# Talko_1_1.net
KiCad netlist of a schematic drawn in EAGLE
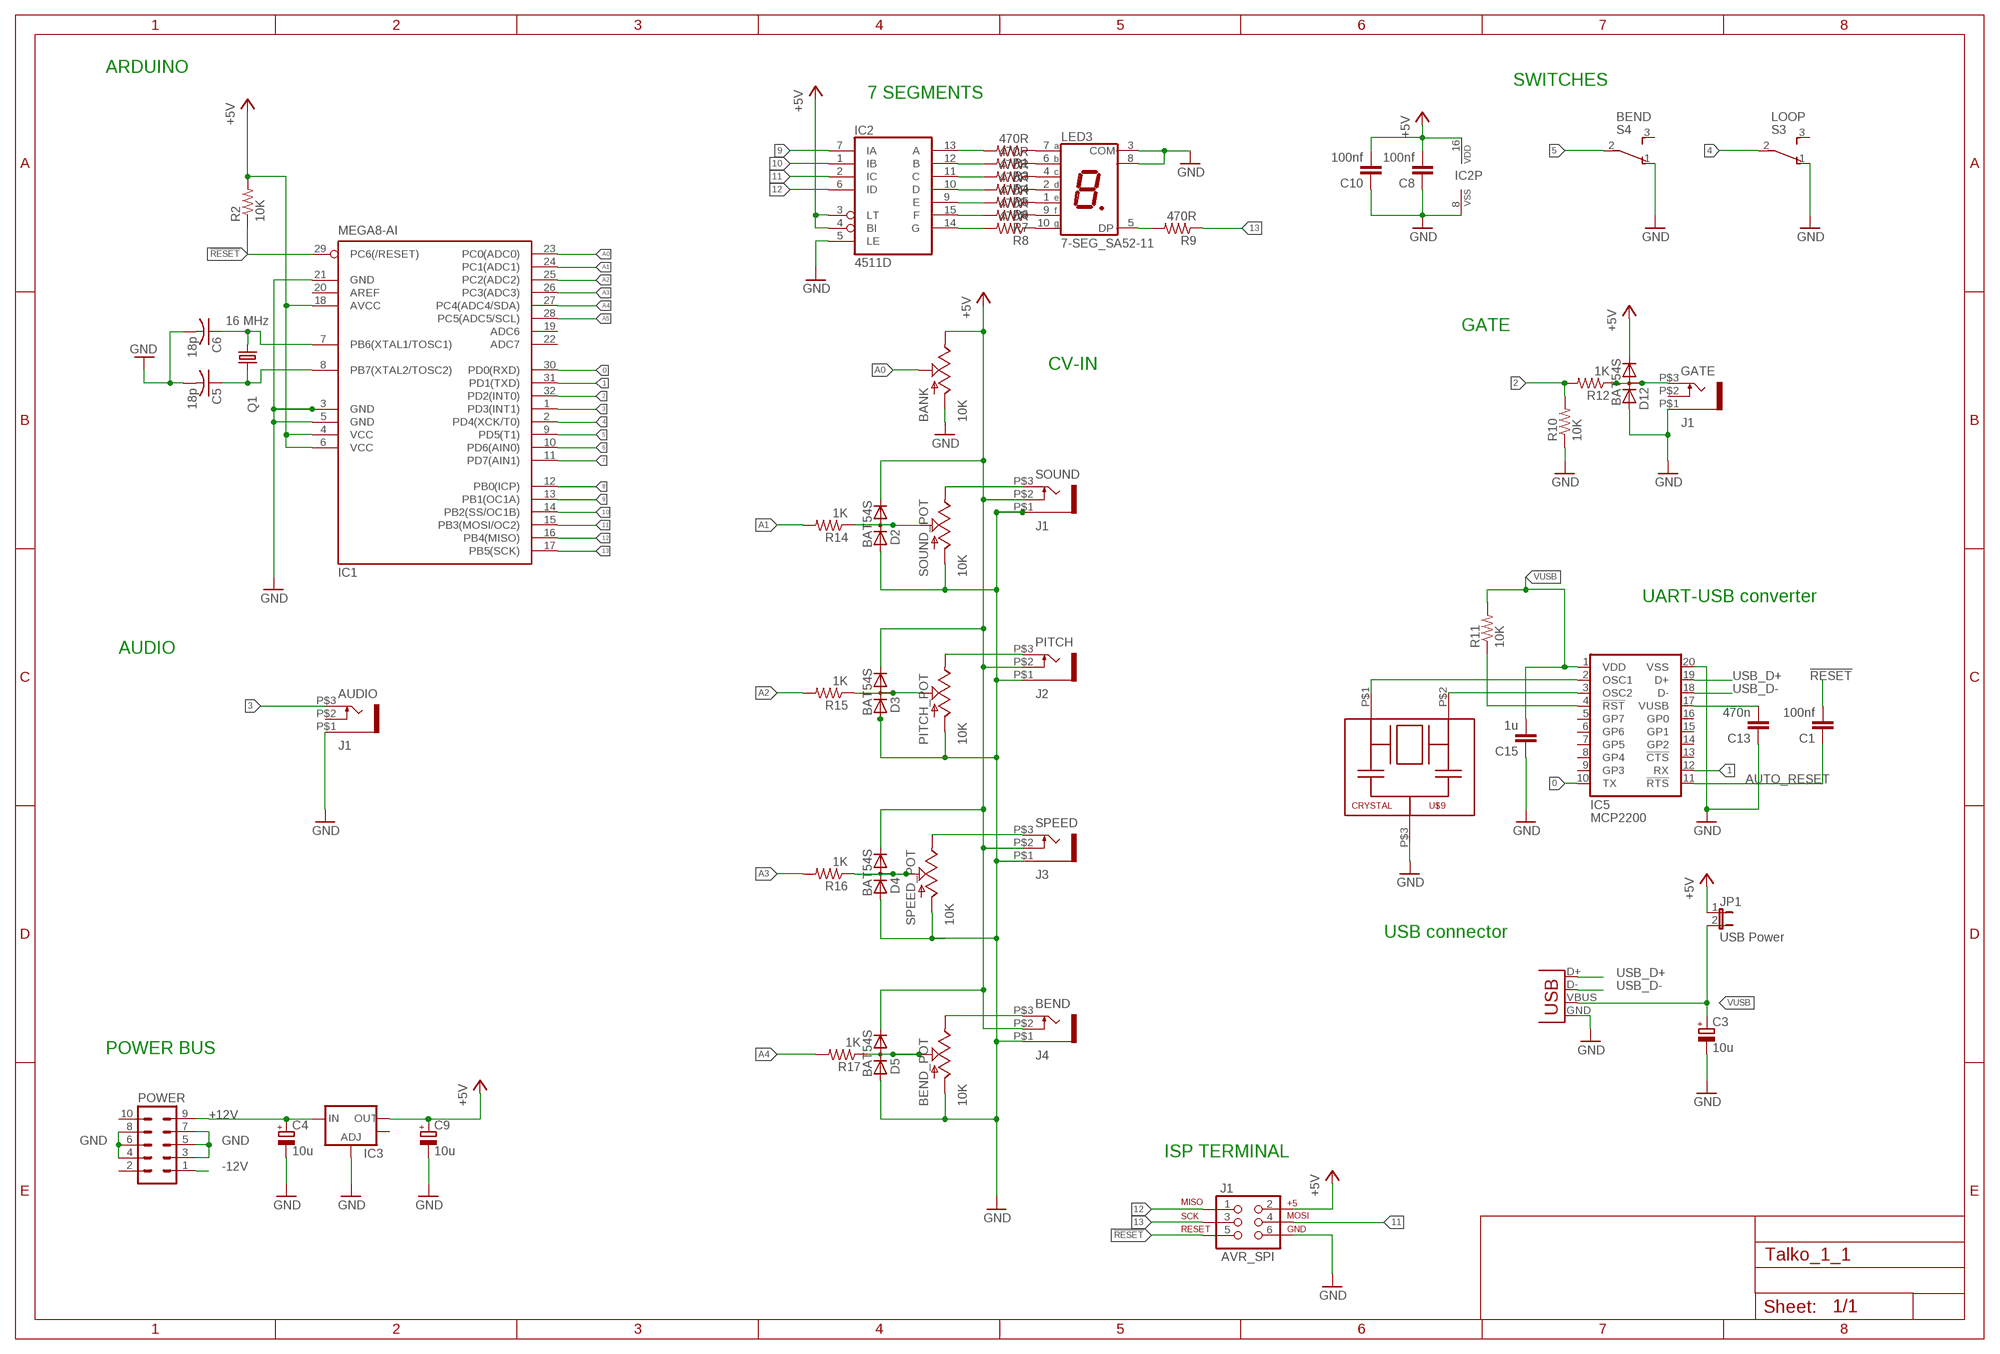
[diagram p0: schematic, sheet 1]

(export (version "E")
  (design (tool "Eeschema 10.0.6"))
  (components
    (comp (ref "AUDIO")
      (value "J1")
      (footprint "eagle-import:THONKICONN")
      (libsource (lib "eagle-import") (part "THONKICONN"))
    )
    (comp (ref "BANK")
      (value "10K")
      (footprint "eagle-import:ALPS_POT")
      (libsource (lib "eagle-import") (part "POT"))
    )
    (comp (ref "BEND")
      (value "J4")
      (footprint "eagle-import:THONKICONN")
      (libsource (lib "eagle-import") (part "THONKICONN"))
    )
    (comp (ref "BEND_POT")
      (value "10K")
      (footprint "eagle-import:ALPS_POT")
      (libsource (lib "eagle-import") (part "POT"))
    )
    (comp (ref "C1")
      (value "100nf")
      (footprint "eagle-import:C0805")
      (libsource (lib "eagle-import") (part "C-EUC0805"))
    )
    (comp (ref "C3")
      (value "10u")
      (footprint "eagle-import:R_2012-12R")
      (libsource (lib "eagle-import") (part "CPOL-EUR/2012-12R"))
    )
    (comp (ref "C4")
      (value "10u")
      (footprint "eagle-import:R_2012-12R")
      (libsource (lib "eagle-import") (part "CPOL-EUR/2012-12R"))
    )
    (comp (ref "C5")
      (value "18p")
      (footprint "eagle-import:C0805K")
      (libsource (lib "eagle-import") (part "C-USC0805K"))
    )
    (comp (ref "C6")
      (value "18p")
      (footprint "eagle-import:C0805K")
      (libsource (lib "eagle-import") (part "C-USC0805K"))
    )
    (comp (ref "C8")
      (value "100nf")
      (footprint "eagle-import:C0805")
      (libsource (lib "eagle-import") (part "C-EUC0805"))
    )
    (comp (ref "C9")
      (value "10u")
      (footprint "eagle-import:R_2012-12R")
      (libsource (lib "eagle-import") (part "CPOL-EUR/2012-12R"))
    )
    (comp (ref "C10")
      (value "100nf")
      (footprint "eagle-import:C0805")
      (libsource (lib "eagle-import") (part "C-EUC0805"))
    )
    (comp (ref "C13")
      (value "470n")
      (footprint "eagle-import:0805")
      (libsource (lib "eagle-import") (part "CAP0805"))
    )
    (comp (ref "C15")
      (value "1u")
      (footprint "eagle-import:0805")
      (libsource (lib "eagle-import") (part "CAP0805"))
    )
    (comp (ref "D2")
      (value "BAT54S")
      (footprint "eagle-import:SOT23")
      (libsource (lib "eagle-import") (part "DIODE_2CACA-SOT23"))
    )
    (comp (ref "D3")
      (value "BAT54S")
      (footprint "eagle-import:SOT23")
      (libsource (lib "eagle-import") (part "DIODE_2CACA-SOT23"))
    )
    (comp (ref "D4")
      (value "BAT54S")
      (footprint "eagle-import:SOT23")
      (libsource (lib "eagle-import") (part "DIODE_2CACA-SOT23"))
    )
    (comp (ref "D5")
      (value "BAT54S")
      (footprint "eagle-import:SOT23")
      (libsource (lib "eagle-import") (part "DIODE_2CACA-SOT23"))
    )
    (comp (ref "D12")
      (value "BAT54S")
      (footprint "eagle-import:SOT23")
      (libsource (lib "eagle-import") (part "DIODE_2CACA-SOT23"))
    )
    (comp (ref "GATE")
      (value "J1")
      (footprint "eagle-import:THONKICONN")
      (libsource (lib "eagle-import") (part "THONKICONN"))
    )
    (comp (ref "IC1")
      (value "MEGA8-AI")
      (footprint "eagle-import:TQFP32-08")
      (fields (field (name "MPN") "ATMEGA8-16AU"))
      (libsource (lib "eagle-import") (part "MEGA8-AI"))
    )
    (comp (ref "IC2")
      (value "4511D")
      (footprint "eagle-import:SO16")
      (fields (field (name "OC_MOUSER") "863-MC14511BDG"))
      (libsource (lib "eagle-import") (part "4511D"))
    )
    (comp (ref "IC3")
      (value "V_REG_LM1117SOT223")
      (footprint "eagle-import:SOT223")
      (libsource (lib "eagle-import") (part "V_REG_LM1117SOT223"))
    )
    (comp (ref "IC5")
      (value "MCP2200")
      (footprint "eagle-import:SO20")
      (libsource (lib "eagle-import") (part "MCP2200"))
    )
    (comp (ref "J1")
      (value "AVR_SPI")
      (footprint "eagle-import:2X3_LOCK")
      (libsource (lib "eagle-import") (part "AVR_SPI_PRG_62X3_LOCK"))
    )
    (comp (ref "JP1")
      (value "USB Power")
      (footprint "eagle-import:JP1")
      (libsource (lib "eagle-import") (part "JP1E"))
    )
    (comp (ref "LED3")
      (value "7-SEG_SA52-11")
      (footprint "eagle-import:SA52-11")
      (fields (field (name "OC_FARNELL") "1168602"))
      (libsource (lib "eagle-import") (part "7-SEG_SA52-11"))
    )
    (comp (ref "PITCH")
      (value "J2")
      (footprint "eagle-import:THONKICONN")
      (libsource (lib "eagle-import") (part "THONKICONN"))
    )
    (comp (ref "PITCH_POT")
      (value "10K")
      (footprint "eagle-import:ALPS_POT")
      (libsource (lib "eagle-import") (part "POT"))
    )
    (comp (ref "POWER")
      (value "10_PIN_HEADER")
      (footprint "eagle-import:MA05-2")
      (libsource (lib "eagle-import") (part "10_PIN_HEADER"))
    )
    (comp (ref "Q1")
      (value "16 MHz")
      (footprint "eagle-import:CTS406")
      (libsource (lib "eagle-import") (part "CRYSTALCTS406"))
    )
    (comp (ref "R1")
      (value "470R")
      (footprint "eagle-import:M0805")
      (libsource (lib "eagle-import") (part "R-US_M0805"))
    )
    (comp (ref "R2")
      (value "10K")
      (footprint "eagle-import:M0805")
      (libsource (lib "eagle-import") (part "R-US_M0805"))
    )
    (comp (ref "R3")
      (value "470R")
      (footprint "eagle-import:M0805")
      (libsource (lib "eagle-import") (part "R-US_M0805"))
    )
    (comp (ref "R4")
      (value "470R")
      (footprint "eagle-import:M0805")
      (libsource (lib "eagle-import") (part "R-US_M0805"))
    )
    (comp (ref "R5")
      (value "470R")
      (footprint "eagle-import:M0805")
      (libsource (lib "eagle-import") (part "R-US_M0805"))
    )
    (comp (ref "R6")
      (value "470R")
      (footprint "eagle-import:M0805")
      (libsource (lib "eagle-import") (part "R-US_M0805"))
    )
    (comp (ref "R7")
      (value "470R")
      (footprint "eagle-import:M0805")
      (libsource (lib "eagle-import") (part "R-US_M0805"))
    )
    (comp (ref "R8")
      (value "470R")
      (footprint "eagle-import:M0805")
      (libsource (lib "eagle-import") (part "R-US_M0805"))
    )
    (comp (ref "R9")
      (value "470R")
      (footprint "eagle-import:M0805")
      (libsource (lib "eagle-import") (part "R-US_M0805"))
    )
    (comp (ref "R10")
      (value "10K")
      (footprint "eagle-import:M0805")
      (libsource (lib "eagle-import") (part "R-US_M0805"))
    )
    (comp (ref "R11")
      (value "10K")
      (footprint "eagle-import:M0805")
      (libsource (lib "eagle-import") (part "R-US_M0805"))
    )
    (comp (ref "R12")
      (value "1K")
      (footprint "eagle-import:M0805")
      (libsource (lib "eagle-import") (part "R-US_M0805"))
    )
    (comp (ref "R14")
      (value "1K")
      (footprint "eagle-import:M0805")
      (libsource (lib "eagle-import") (part "R-US_M0805"))
    )
    (comp (ref "R15")
      (value "1K")
      (footprint "eagle-import:M0805")
      (libsource (lib "eagle-import") (part "R-US_M0805"))
    )
    (comp (ref "R16")
      (value "1K")
      (footprint "eagle-import:M0805")
      (libsource (lib "eagle-import") (part "R-US_M0805"))
    )
    (comp (ref "R17")
      (value "1K")
      (footprint "eagle-import:M0805")
      (libsource (lib "eagle-import") (part "R-US_M0805"))
    )
    (comp (ref "S3")
      (value "LOOP")
      (footprint "eagle-import:TL3XPO")
      (libsource (lib "eagle-import") (part "TL36PO"))
    )
    (comp (ref "S4")
      (value "BEND")
      (footprint "eagle-import:TL3XPO")
      (libsource (lib "eagle-import") (part "TL36PO"))
    )
    (comp (ref "SOUND")
      (value "J1")
      (footprint "eagle-import:THONKICONN")
      (libsource (lib "eagle-import") (part "THONKICONN"))
    )
    (comp (ref "SOUND_POT")
      (value "10K")
      (footprint "eagle-import:ALPS_POT")
      (libsource (lib "eagle-import") (part "POT"))
    )
    (comp (ref "SPEED")
      (value "J3")
      (footprint "eagle-import:THONKICONN")
      (libsource (lib "eagle-import") (part "THONKICONN"))
    )
    (comp (ref "SPEED_POT")
      (value "10K")
      (footprint "eagle-import:ALPS_POT")
      (libsource (lib "eagle-import") (part "POT"))
    )
    (comp (ref "U$9")
      (value "CRYSTAL")
      (footprint "eagle-import:CRYSTAL")
      (libsource (lib "eagle-import") (part "CRYSTAL"))
    )
    (comp (ref "X3")
      (value "USB")
      (footprint "eagle-import:USB-B-PTH-VERTICAL")
      (libsource (lib "eagle-import") (part "USBPTH-VERTICAL"))
    )
  )
  (nets
    (net (code "1") (name "+5V") (class "Default")
      (node (ref "BANK") (pin "P$1") (pinfunction "E_P$1") (pintype "passive"))
      (node (ref "BEND") (pin "P$2") (pinfunction "4_P$2") (pintype "passive"))
      (node (ref "C10") (pin "2") (pinfunction "2_2") (pintype "passive"))
      (node (ref "C8") (pin "2") (pinfunction "2_2") (pintype "passive"))
      (node (ref "C9") (pin "+") (pinfunction "+_+") (pintype "passive"))
      (node (ref "D12") (pin "2") (pinfunction "C_2") (pintype "passive"))
      (node (ref "D2") (pin "2") (pinfunction "C_2") (pintype "passive"))
      (node (ref "D3") (pin "2") (pinfunction "C_2") (pintype "passive"))
      (node (ref "D4") (pin "2") (pinfunction "C_2") (pintype "passive"))
      (node (ref "D5") (pin "2") (pinfunction "C_2") (pintype "passive"))
      (node (ref "IC1") (pin "18") (pinfunction "AVCC_18") (pintype "power_in"))
      (node (ref "IC1") (pin "4") (pinfunction "VCC_4") (pintype "power_in"))
      (node (ref "IC1") (pin "6") (pinfunction "VCC_6") (pintype "power_in"))
      (node (ref "IC2") (pin "16") (pinfunction "VDD_16") (pintype "power_in"))
      (node (ref "IC2") (pin "3") (pinfunction "LT_3") (pintype "input"))
      (node (ref "IC2") (pin "4") (pinfunction "BI_4") (pintype "input"))
      (node (ref "IC3") (pin "2") (pinfunction "OUT_2") (pintype "output"))
      (node (ref "J1") (pin "2") (pinfunction "2_2") (pintype "passive"))
      (node (ref "JP1") (pin "1") (pinfunction "1_1") (pintype "passive"))
      (node (ref "PITCH") (pin "P$2") (pinfunction "4_P$2") (pintype "passive"))
      (node (ref "R2") (pin "2") (pinfunction "2_2") (pintype "passive"))
      (node (ref "SOUND") (pin "P$2") (pinfunction "4_P$2") (pintype "passive"))
      (node (ref "SPEED") (pin "P$2") (pinfunction "4_P$2") (pintype "passive"))
    )
    (net (code "2") (name "/+12V") (class "Default")
      (node (ref "C4") (pin "+") (pinfunction "+_+") (pintype "passive"))
      (node (ref "IC3") (pin "3") (pinfunction "IN_3") (pintype "input"))
      (node (ref "POWER") (pin "9") (pinfunction "9_9") (pintype "passive"))
    )
    (net (code "3") (name "/-12V") (class "Default")
      (node (ref "POWER") (pin "1") (pinfunction "1_1") (pintype "passive"))
    )
    (net (code "4") (name "/AUTO_RESET") (class "Default")
      (node (ref "C1") (pin "1") (pinfunction "1_1") (pintype "passive"))
      (node (ref "IC5") (pin "11") (pinfunction "~{RTS}_11") (pintype "bidirectional"))
    )
    (net (code "5") (name "/USB_D+") (class "Default")
      (node (ref "IC5") (pin "19") (pinfunction "D+_19") (pintype "bidirectional"))
      (node (ref "X3") (pin "D+") (pinfunction "D+_D+") (pintype "bidirectional"))
    )
    (net (code "6") (name "/USB_D-") (class "Default")
      (node (ref "IC5") (pin "18") (pinfunction "D-_18") (pintype "bidirectional"))
      (node (ref "X3") (pin "D-") (pinfunction "D-_D-") (pintype "bidirectional"))
    )
    (net (code "7") (name "/~{RESET}") (class "Default")
      (node (ref "C1") (pin "2") (pinfunction "2_2") (pintype "passive"))
      (node (ref "IC1") (pin "29") (pinfunction "PC6(/RESET)_29") (pintype "bidirectional"))
      (node (ref "J1") (pin "5") (pinfunction "5_5") (pintype "passive"))
      (node (ref "R2") (pin "1") (pinfunction "1_1") (pintype "passive"))
    )
    (net (code "8") (name "0") (class "Default")
      (node (ref "IC1") (pin "30") (pinfunction "PD0(RXD)_30") (pintype "bidirectional"))
      (node (ref "IC5") (pin "10") (pinfunction "TX_10") (pintype "bidirectional"))
    )
    (net (code "9") (name "1") (class "Default")
      (node (ref "IC1") (pin "31") (pinfunction "PD1(TXD)_31") (pintype "bidirectional"))
      (node (ref "IC5") (pin "12") (pinfunction "RX_12") (pintype "bidirectional"))
    )
    (net (code "10") (name "2") (class "Default")
      (node (ref "IC1") (pin "32") (pinfunction "PD2(INT0)_32") (pintype "bidirectional"))
      (node (ref "R10") (pin "2") (pinfunction "2_2") (pintype "passive"))
      (node (ref "R12") (pin "2") (pinfunction "2_2") (pintype "passive"))
    )
    (net (code "11") (name "3") (class "Default")
      (node (ref "AUDIO") (pin "P$3") (pinfunction "3_P$3") (pintype "passive"))
      (node (ref "IC1") (pin "1") (pinfunction "PD3(INT1)_1") (pintype "bidirectional"))
    )
    (net (code "12") (name "4") (class "Default")
      (node (ref "IC1") (pin "2") (pinfunction "PD4(XCK/T0)_2") (pintype "bidirectional"))
      (node (ref "S3") (pin "2") (pinfunction "P_2") (pintype "passive"))
    )
    (net (code "13") (name "5") (class "Default")
      (node (ref "IC1") (pin "9") (pinfunction "PD5(T1)_9") (pintype "bidirectional"))
      (node (ref "S4") (pin "2") (pinfunction "P_2") (pintype "passive"))
    )
    (net (code "14") (name "6") (class "Default")
      (node (ref "IC1") (pin "10") (pinfunction "PD6(AIN0)_10") (pintype "bidirectional"))
    )
    (net (code "15") (name "7") (class "Default")
      (node (ref "IC1") (pin "11") (pinfunction "PD7(AIN1)_11") (pintype "bidirectional"))
    )
    (net (code "16") (name "8") (class "Default")
      (node (ref "IC1") (pin "12") (pinfunction "PB0(ICP)_12") (pintype "bidirectional"))
    )
    (net (code "17") (name "9") (class "Default")
      (node (ref "IC1") (pin "13") (pinfunction "PB1(OC1A)_13") (pintype "bidirectional"))
      (node (ref "IC2") (pin "7") (pinfunction "IA_7") (pintype "input"))
    )
    (net (code "18") (name "10") (class "Default")
      (node (ref "IC1") (pin "14") (pinfunction "PB2(SS/OC1B)_14") (pintype "bidirectional"))
      (node (ref "IC2") (pin "1") (pinfunction "IB_1") (pintype "input"))
    )
    (net (code "19") (name "11") (class "Default")
      (node (ref "IC1") (pin "15") (pinfunction "PB3(MOSI/OC2)_15") (pintype "bidirectional"))
      (node (ref "IC2") (pin "2") (pinfunction "IC_2") (pintype "input"))
      (node (ref "J1") (pin "4") (pinfunction "4_4") (pintype "passive"))
    )
    (net (code "20") (name "12") (class "Default")
      (node (ref "IC1") (pin "16") (pinfunction "PB4(MISO)_16") (pintype "bidirectional"))
      (node (ref "IC2") (pin "6") (pinfunction "ID_6") (pintype "input"))
      (node (ref "J1") (pin "1") (pinfunction "1_1") (pintype "passive"))
    )
    (net (code "21") (name "13") (class "Default")
      (node (ref "IC1") (pin "17") (pinfunction "PB5(SCK)_17") (pintype "bidirectional"))
      (node (ref "J1") (pin "3") (pinfunction "3_3") (pintype "passive"))
      (node (ref "R9") (pin "1") (pinfunction "1_1") (pintype "passive"))
    )
    (net (code "22") (name "A0") (class "Default")
      (node (ref "BANK") (pin "P$2") (pinfunction "S_P$2") (pintype "passive"))
      (node (ref "IC1") (pin "23") (pinfunction "PC0(ADC0)_23") (pintype "bidirectional"))
    )
    (net (code "23") (name "A1") (class "Default")
      (node (ref "IC1") (pin "24") (pinfunction "PC1(ADC1)_24") (pintype "bidirectional"))
      (node (ref "R14") (pin "2") (pinfunction "2_2") (pintype "passive"))
    )
    (net (code "24") (name "A2") (class "Default")
      (node (ref "IC1") (pin "25") (pinfunction "PC2(ADC2)_25") (pintype "bidirectional"))
      (node (ref "R15") (pin "2") (pinfunction "2_2") (pintype "passive"))
    )
    (net (code "25") (name "A3") (class "Default")
      (node (ref "IC1") (pin "26") (pinfunction "PC3(ADC3)_26") (pintype "bidirectional"))
      (node (ref "R16") (pin "2") (pinfunction "2_2") (pintype "passive"))
    )
    (net (code "26") (name "A4") (class "Default")
      (node (ref "IC1") (pin "27") (pinfunction "PC4(ADC4/SDA)_27") (pintype "bidirectional"))
      (node (ref "R17") (pin "2") (pinfunction "2_2") (pintype "passive"))
    )
    (net (code "27") (name "A5") (class "Default")
      (node (ref "IC1") (pin "28") (pinfunction "PC5(ADC5/SCL)_28") (pintype "bidirectional"))
    )
    (net (code "28") (name "GND") (class "Default")
      (node (ref "AUDIO") (pin "P$1") (pinfunction "5_P$1") (pintype "passive"))
      (node (ref "BANK") (pin "P$3") (pinfunction "A_P$3") (pintype "passive"))
      (node (ref "BEND") (pin "P$1") (pinfunction "5_P$1") (pintype "passive"))
      (node (ref "BEND_POT") (pin "P$3") (pinfunction "A_P$3") (pintype "passive"))
      (node (ref "C10") (pin "1") (pinfunction "1_1") (pintype "passive"))
      (node (ref "C13") (pin "1") (pinfunction "1_1") (pintype "passive"))
      (node (ref "C15") (pin "1") (pinfunction "1_1") (pintype "passive"))
      (node (ref "C3") (pin "-") (pinfunction "-_-") (pintype "passive"))
      (node (ref "C4") (pin "-") (pinfunction "-_-") (pintype "passive"))
      (node (ref "C5") (pin "2") (pinfunction "2_2") (pintype "passive"))
      (node (ref "C6") (pin "2") (pinfunction "2_2") (pintype "passive"))
      (node (ref "C8") (pin "1") (pinfunction "1_1") (pintype "passive"))
      (node (ref "C9") (pin "-") (pinfunction "-_-") (pintype "passive"))
      (node (ref "D12") (pin "1") (pinfunction "A_1") (pintype "passive"))
      (node (ref "D2") (pin "1") (pinfunction "A_1") (pintype "passive"))
      (node (ref "D3") (pin "1") (pinfunction "A_1") (pintype "passive"))
      (node (ref "D4") (pin "1") (pinfunction "A_1") (pintype "passive"))
      (node (ref "D5") (pin "1") (pinfunction "A_1") (pintype "passive"))
      (node (ref "GATE") (pin "P$1") (pinfunction "5_P$1") (pintype "passive"))
      (node (ref "IC1") (pin "21") (pinfunction "GND_21") (pintype "power_in"))
      (node (ref "IC1") (pin "3") (pinfunction "GND_3") (pintype "power_in"))
      (node (ref "IC1") (pin "5") (pinfunction "GND_5") (pintype "power_in"))
      (node (ref "IC2") (pin "5") (pinfunction "LE_5") (pintype "input"))
      (node (ref "IC2") (pin "8") (pinfunction "VSS_8") (pintype "power_in"))
      (node (ref "IC3") (pin "1") (pinfunction "ADJ_1") (pintype "input"))
      (node (ref "IC5") (pin "20") (pinfunction "VSS_20") (pintype "power_in"))
      (node (ref "J1") (pin "6") (pinfunction "6_6") (pintype "passive"))
      (node (ref "LED3") (pin "3") (pinfunction "COM_3") (pintype "passive"))
      (node (ref "LED3") (pin "8") (pinfunction "COM_8") (pintype "passive"))
      (node (ref "PITCH") (pin "P$1") (pinfunction "5_P$1") (pintype "passive"))
      (node (ref "PITCH_POT") (pin "P$3") (pinfunction "A_P$3") (pintype "passive"))
      (node (ref "POWER") (pin "3") (pinfunction "3_3") (pintype "passive"))
      (node (ref "POWER") (pin "4") (pinfunction "4_4") (pintype "passive"))
      (node (ref "POWER") (pin "5") (pinfunction "5_5") (pintype "passive"))
      (node (ref "POWER") (pin "6") (pinfunction "6_6") (pintype "passive"))
      (node (ref "POWER") (pin "7") (pinfunction "7_7") (pintype "passive"))
      (node (ref "POWER") (pin "8") (pinfunction "8_8") (pintype "passive"))
      (node (ref "R10") (pin "1") (pinfunction "1_1") (pintype "passive"))
      (node (ref "S3") (pin "1") (pinfunction "O_1") (pintype "passive"))
      (node (ref "S4") (pin "1") (pinfunction "O_1") (pintype "passive"))
      (node (ref "SOUND") (pin "P$1") (pinfunction "5_P$1") (pintype "passive"))
      (node (ref "SOUND_POT") (pin "P$3") (pinfunction "A_P$3") (pintype "passive"))
      (node (ref "SPEED") (pin "P$1") (pinfunction "5_P$1") (pintype "passive"))
      (node (ref "SPEED_POT") (pin "P$3") (pinfunction "A_P$3") (pintype "passive"))
      (node (ref "U$9") (pin "P$3") (pinfunction "3_P$3") (pintype "bidirectional"))
      (node (ref "X3") (pin "GND") (pinfunction "GND_GND") (pintype "bidirectional"))
    )
    (net (code "29") (name "Net-(BEND-3)") (class "Default")
      (node (ref "BEND") (pin "P$3") (pinfunction "3_P$3") (pintype "passive"))
      (node (ref "BEND_POT") (pin "P$1") (pinfunction "E_P$1") (pintype "passive"))
    )
    (net (code "30") (name "Net-(BEND_POT-S)") (class "Default")
      (node (ref "BEND_POT") (pin "P$2") (pinfunction "S_P$2") (pintype "passive"))
      (node (ref "D5") (pin "3") (pinfunction "AC_3") (pintype "passive"))
      (node (ref "R17") (pin "1") (pinfunction "1_1") (pintype "passive"))
    )
    (net (code "31") (name "Net-(D2-AC)") (class "Default")
      (node (ref "D2") (pin "3") (pinfunction "AC_3") (pintype "passive"))
      (node (ref "R14") (pin "1") (pinfunction "1_1") (pintype "passive"))
      (node (ref "SOUND_POT") (pin "P$2") (pinfunction "S_P$2") (pintype "passive"))
    )
    (net (code "32") (name "Net-(D3-AC)") (class "Default")
      (node (ref "D3") (pin "3") (pinfunction "AC_3") (pintype "passive"))
      (node (ref "PITCH_POT") (pin "P$2") (pinfunction "S_P$2") (pintype "passive"))
      (node (ref "R15") (pin "1") (pinfunction "1_1") (pintype "passive"))
    )
    (net (code "33") (name "Net-(D4-AC)") (class "Default")
      (node (ref "D4") (pin "3") (pinfunction "AC_3") (pintype "passive"))
      (node (ref "R16") (pin "1") (pinfunction "1_1") (pintype "passive"))
      (node (ref "SPEED_POT") (pin "P$2") (pinfunction "S_P$2") (pintype "passive"))
    )
    (net (code "34") (name "Net-(D12-AC)") (class "Default")
      (node (ref "D12") (pin "3") (pinfunction "AC_3") (pintype "passive"))
      (node (ref "GATE") (pin "P$3") (pinfunction "3_P$3") (pintype "passive"))
      (node (ref "R12") (pin "1") (pinfunction "1_1") (pintype "passive"))
    )
    (net (code "35") (name "Net-(IC1-PB6(XTAL1{slash}TOSC1))") (class "Default")
      (node (ref "C6") (pin "1") (pinfunction "1_1") (pintype "passive"))
      (node (ref "IC1") (pin "7") (pinfunction "PB6(XTAL1/TOSC1)_7") (pintype "bidirectional"))
      (node (ref "Q1") (pin "3") (pinfunction "2_3") (pintype "passive"))
    )
    (net (code "36") (name "Net-(IC1-PB7(XTAL2{slash}TOSC2))") (class "Default")
      (node (ref "C5") (pin "1") (pinfunction "1_1") (pintype "passive"))
      (node (ref "IC1") (pin "8") (pinfunction "PB7(XTAL2/TOSC2)_8") (pintype "bidirectional"))
      (node (ref "Q1") (pin "1") (pinfunction "1_1") (pintype "passive"))
    )
    (net (code "37") (name "Net-(IC2A-A)") (class "Default")
      (node (ref "IC2") (pin "13") (pinfunction "A_13") (pintype "output"))
      (node (ref "R1") (pin "2") (pinfunction "2_2") (pintype "passive"))
    )
    (net (code "38") (name "Net-(IC2A-B)") (class "Default")
      (node (ref "IC2") (pin "12") (pinfunction "B_12") (pintype "output"))
      (node (ref "R3") (pin "2") (pinfunction "2_2") (pintype "passive"))
    )
    (net (code "39") (name "Net-(IC2A-C)") (class "Default")
      (node (ref "IC2") (pin "11") (pinfunction "C_11") (pintype "output"))
      (node (ref "R4") (pin "2") (pinfunction "2_2") (pintype "passive"))
    )
    (net (code "40") (name "Net-(IC2A-D)") (class "Default")
      (node (ref "IC2") (pin "10") (pinfunction "D_10") (pintype "output"))
      (node (ref "R5") (pin "2") (pinfunction "2_2") (pintype "passive"))
    )
    (net (code "41") (name "Net-(IC2A-E)") (class "Default")
      (node (ref "IC2") (pin "9") (pinfunction "E_9") (pintype "output"))
      (node (ref "R6") (pin "2") (pinfunction "2_2") (pintype "passive"))
    )
    (net (code "42") (name "Net-(IC2A-F)") (class "Default")
      (node (ref "IC2") (pin "15") (pinfunction "F_15") (pintype "output"))
      (node (ref "R7") (pin "2") (pinfunction "2_2") (pintype "passive"))
    )
    (net (code "43") (name "Net-(IC2A-G)") (class "Default")
      (node (ref "IC2") (pin "14") (pinfunction "G_14") (pintype "output"))
      (node (ref "R8") (pin "2") (pinfunction "2_2") (pintype "passive"))
    )
    (net (code "44") (name "Net-(IC5-OSC1)") (class "Default")
      (node (ref "IC5") (pin "2") (pinfunction "OSC1_2") (pintype "bidirectional"))
      (node (ref "U$9") (pin "P$1") (pinfunction "1_P$1") (pintype "bidirectional"))
    )
    (net (code "45") (name "Net-(IC5-OSC2)") (class "Default")
      (node (ref "IC5") (pin "3") (pinfunction "OSC2_3") (pintype "bidirectional"))
      (node (ref "U$9") (pin "P$2") (pinfunction "2_P$2") (pintype "bidirectional"))
    )
    (net (code "46") (name "Net-(IC5-VUSB)") (class "Default")
      (node (ref "C13") (pin "2") (pinfunction "2_2") (pintype "passive"))
      (node (ref "IC5") (pin "17") (pinfunction "VUSB_17") (pintype "bidirectional"))
    )
    (net (code "47") (name "Net-(IC5-~{RST})") (class "Default")
      (node (ref "IC5") (pin "4") (pinfunction "~{RST}_4") (pintype "bidirectional"))
      (node (ref "R11") (pin "1") (pinfunction "1_1") (pintype "passive"))
    )
    (net (code "48") (name "Net-(LED3-A)") (class "Default")
      (node (ref "LED3") (pin "7") (pinfunction "A_7") (pintype "passive"))
      (node (ref "R1") (pin "1") (pinfunction "1_1") (pintype "passive"))
    )
    (net (code "49") (name "Net-(LED3-B)") (class "Default")
      (node (ref "LED3") (pin "6") (pinfunction "B_6") (pintype "passive"))
      (node (ref "R3") (pin "1") (pinfunction "1_1") (pintype "passive"))
    )
    (net (code "50") (name "Net-(LED3-C)") (class "Default")
      (node (ref "LED3") (pin "4") (pinfunction "C_4") (pintype "passive"))
      (node (ref "R4") (pin "1") (pinfunction "1_1") (pintype "passive"))
    )
    (net (code "51") (name "Net-(LED3-D)") (class "Default")
      (node (ref "LED3") (pin "2") (pinfunction "D_2") (pintype "passive"))
      (node (ref "R5") (pin "1") (pinfunction "1_1") (pintype "passive"))
    )
    (net (code "52") (name "Net-(LED3-DP)") (class "Default")
      (node (ref "LED3") (pin "5") (pinfunction "DP_5") (pintype "passive"))
      (node (ref "R9") (pin "2") (pinfunction "2_2") (pintype "passive"))
    )
    (net (code "53") (name "Net-(LED3-E)") (class "Default")
      (node (ref "LED3") (pin "1") (pinfunction "E_1") (pintype "passive"))
      (node (ref "R6") (pin "1") (pinfunction "1_1") (pintype "passive"))
    )
    (net (code "54") (name "Net-(LED3-F)") (class "Default")
      (node (ref "LED3") (pin "9") (pinfunction "F_9") (pintype "passive"))
      (node (ref "R7") (pin "1") (pinfunction "1_1") (pintype "passive"))
    )
    (net (code "55") (name "Net-(LED3-G)") (class "Default")
      (node (ref "LED3") (pin "10") (pinfunction "G_10") (pintype "passive"))
      (node (ref "R8") (pin "1") (pinfunction "1_1") (pintype "passive"))
    )
    (net (code "56") (name "Net-(PITCH-3)") (class "Default")
      (node (ref "PITCH") (pin "P$3") (pinfunction "3_P$3") (pintype "passive"))
      (node (ref "PITCH_POT") (pin "P$1") (pinfunction "E_P$1") (pintype "passive"))
    )
    (net (code "57") (name "Net-(SOUND-3)") (class "Default")
      (node (ref "SOUND") (pin "P$3") (pinfunction "3_P$3") (pintype "passive"))
      (node (ref "SOUND_POT") (pin "P$1") (pinfunction "E_P$1") (pintype "passive"))
    )
    (net (code "58") (name "Net-(SPEED-3)") (class "Default")
      (node (ref "SPEED") (pin "P$3") (pinfunction "3_P$3") (pintype "passive"))
      (node (ref "SPEED_POT") (pin "P$1") (pinfunction "E_P$1") (pintype "passive"))
    )
    (net (code "59") (name "VUSB") (class "Default")
      (node (ref "C15") (pin "2") (pinfunction "2_2") (pintype "passive"))
      (node (ref "C3") (pin "+") (pinfunction "+_+") (pintype "passive"))
      (node (ref "IC5") (pin "1") (pinfunction "VDD_1") (pintype "power_in"))
      (node (ref "JP1") (pin "2") (pinfunction "2_2") (pintype "passive"))
      (node (ref "R11") (pin "2") (pinfunction "2_2") (pintype "passive"))
      (node (ref "X3") (pin "VBUS") (pinfunction "VBUS_VBUS") (pintype "bidirectional"))
    )
    (net (code "60") (name "unconnected-(AUDIO-4-PadP$2)") (class "Default")
      (node (ref "AUDIO") (pin "P$2") (pinfunction "4_P$2") (pintype "passive"))
    )
    (net (code "61") (name "unconnected-(GATE-4-PadP$2)") (class "Default")
      (node (ref "GATE") (pin "P$2") (pinfunction "4_P$2") (pintype "passive"))
    )
    (net (code "62") (name "unconnected-(IC1-ADC6-Pad19)") (class "Default")
      (node (ref "IC1") (pin "19") (pinfunction "ADC6_19") (pintype "bidirectional"))
    )
    (net (code "63") (name "unconnected-(IC1-ADC7-Pad22)") (class "Default")
      (node (ref "IC1") (pin "22") (pinfunction "ADC7_22") (pintype "bidirectional"))
    )
    (net (code "64") (name "unconnected-(IC1-AREF-Pad20)") (class "Default")
      (node (ref "IC1") (pin "20") (pinfunction "AREF_20") (pintype "passive"))
    )
    (net (code "65") (name "unconnected-(IC3-OUT-Pad4)") (class "Default")
      (node (ref "IC3") (pin "4") (pinfunction "OUT_4") (pintype "output"))
    )
    (net (code "66") (name "unconnected-(IC5-GP0-Pad16)") (class "Default")
      (node (ref "IC5") (pin "16") (pinfunction "GP0_16") (pintype "bidirectional"))
    )
    (net (code "67") (name "unconnected-(IC5-GP1-Pad15)") (class "Default")
      (node (ref "IC5") (pin "15") (pinfunction "GP1_15") (pintype "bidirectional"))
    )
    (net (code "68") (name "unconnected-(IC5-GP2-Pad14)") (class "Default")
      (node (ref "IC5") (pin "14") (pinfunction "GP2_14") (pintype "bidirectional"))
    )
    (net (code "69") (name "unconnected-(IC5-GP3-Pad9)") (class "Default")
      (node (ref "IC5") (pin "9") (pinfunction "GP3_9") (pintype "bidirectional"))
    )
    (net (code "70") (name "unconnected-(IC5-GP4-Pad8)") (class "Default")
      (node (ref "IC5") (pin "8") (pinfunction "GP4_8") (pintype "bidirectional"))
    )
    (net (code "71") (name "unconnected-(IC5-GP5-Pad7)") (class "Default")
      (node (ref "IC5") (pin "7") (pinfunction "GP5_7") (pintype "bidirectional"))
    )
    (net (code "72") (name "unconnected-(IC5-GP6-Pad6)") (class "Default")
      (node (ref "IC5") (pin "6") (pinfunction "GP6_6") (pintype "bidirectional"))
    )
    (net (code "73") (name "unconnected-(IC5-GP7-Pad5)") (class "Default")
      (node (ref "IC5") (pin "5") (pinfunction "GP7_5") (pintype "bidirectional"))
    )
    (net (code "74") (name "unconnected-(IC5-~{CTS}-Pad13)") (class "Default")
      (node (ref "IC5") (pin "13") (pinfunction "~{CTS}_13") (pintype "bidirectional"))
    )
    (net (code "75") (name "unconnected-(POWER-Pad2)") (class "Default")
      (node (ref "POWER") (pin "2") (pinfunction "2_2") (pintype "passive"))
    )
    (net (code "76") (name "unconnected-(POWER-Pad10)") (class "Default")
      (node (ref "POWER") (pin "10") (pinfunction "10_10") (pintype "passive"))
    )
    (net (code "77") (name "unconnected-(S3-S-Pad3)") (class "Default")
      (node (ref "S3") (pin "3") (pinfunction "S_3") (pintype "passive"))
    )
    (net (code "78") (name "unconnected-(S4-S-Pad3)") (class "Default")
      (node (ref "S4") (pin "3") (pinfunction "S_3") (pintype "passive"))
    )
  )
)
